# USB_TYPE_C.net
KiCad netlist of a schematic drawn in Altium Designer
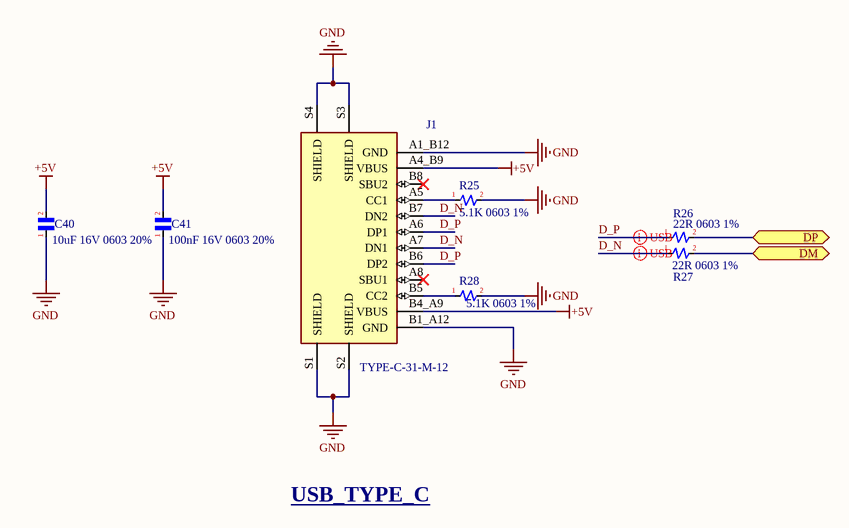
[diagram p0: USB_TYPE_C.SchDoc]

(export (version "E")
  (design (tool "Eeschema 10.0.6"))
  (components
    (comp (ref "C40")
      (value "10uF 16V 0603 20%")
      (footprint "C_0603")
      (description "CAP  0603 20%")
      (libsource (lib "Walton_EED") (part "Capacitor{gt}{gt} Non-Polar"))
    )
    (comp (ref "C41")
      (value "100nF 16V 0603 20%")
      (footprint "C_0603")
      (description "CAP  0603 20%")
      (libsource (lib "Walton_EED") (part "Capacitor{gt}{gt} Non-Polar"))
    )
    (comp (ref "J1")
      (value "TYPE-C-31-M-12")
      (footprint "HRO_TYPE-C-31-M-12")
      (description "USB Connectors 24 Receptacle 1 8.94*7.3mm RoHS")
      (fields (field (name "MF") "HRO Electronics Co., Ltd."))
      (libsource (lib "Walton_EED_13_05_2024") (part "TYPE-C-31-M-12"))
    )
    (comp (ref "R25")
      (value "5.1K 0603 1%")
      (footprint "R_0603")
      (description "RES 0603 20%")
      (libsource (lib "Walton_EED") (part "Resistor{gt}{gt} General Purpose"))
    )
    (comp (ref "R26")
      (value "22R 0603 1%")
      (footprint "R_0603")
      (description "RES 0603 20%")
      (libsource (lib "Walton_EED") (part "Resistor{gt}{gt} General Purpose"))
    )
    (comp (ref "R27")
      (value "22R 0603 1%")
      (footprint "R_0603")
      (description "RES 0603 20%")
      (libsource (lib "Walton_EED") (part "Resistor{gt}{gt} General Purpose"))
    )
    (comp (ref "R28")
      (value "5.1K 0603 1%")
      (footprint "R_0603")
      (description "RES 0603 20%")
      (libsource (lib "Walton_EED") (part "Resistor{gt}{gt} General Purpose"))
    )
  )
  (nets
    (net (code "1") (name "+5V") (class "Default")
      (node (ref "C40") (pin "2") (pinfunction "2_2") (pintype "passive"))
      (node (ref "C41") (pin "2") (pinfunction "2_2") (pintype "passive"))
      (node (ref "J1") (pin "A4_B9") (pinfunction "VBUS_A4_B9") (pintype "power_in"))
      (node (ref "J1") (pin "B4_A9") (pinfunction "VBUS_B4_A9") (pintype "power_in"))
    )
    (net (code "2") (name "/DM") (class "Default")
      (node (ref "R27") (pin "2") (pinfunction "2_2") (pintype "passive"))
    )
    (net (code "3") (name "/DP") (class "Default")
      (node (ref "R26") (pin "2") (pinfunction "2_2") (pintype "passive"))
    )
    (net (code "4") (name "/D_N") (class "Default")
      (node (ref "J1") (pin "A7") (pinfunction "DN1_A7") (pintype "bidirectional"))
      (node (ref "J1") (pin "B7") (pinfunction "DN2_B7") (pintype "bidirectional"))
      (node (ref "R27") (pin "1") (pinfunction "1_1") (pintype "passive"))
    )
    (net (code "5") (name "/D_P") (class "Default")
      (node (ref "J1") (pin "A6") (pinfunction "DP1_A6") (pintype "bidirectional"))
      (node (ref "J1") (pin "B6") (pinfunction "DP2_B6") (pintype "bidirectional"))
      (node (ref "R26") (pin "1") (pinfunction "1_1") (pintype "passive"))
    )
    (net (code "6") (name "GND") (class "Default")
      (node (ref "C40") (pin "1") (pinfunction "1_1") (pintype "passive"))
      (node (ref "C41") (pin "1") (pinfunction "1_1") (pintype "passive"))
      (node (ref "J1") (pin "A1_B12") (pinfunction "GND_A1_B12") (pintype "power_in"))
      (node (ref "J1") (pin "B1_A12") (pinfunction "GND_B1_A12") (pintype "power_in"))
      (node (ref "J1") (pin "S1") (pinfunction "SHIELD_S1") (pintype "passive"))
      (node (ref "J1") (pin "S2") (pinfunction "SHIELD_S2") (pintype "passive"))
      (node (ref "J1") (pin "S3") (pinfunction "SHIELD_S3") (pintype "passive"))
      (node (ref "J1") (pin "S4") (pinfunction "SHIELD_S4") (pintype "passive"))
      (node (ref "R25") (pin "2") (pinfunction "2_2") (pintype "passive"))
      (node (ref "R28") (pin "2") (pinfunction "2_2") (pintype "passive"))
    )
    (net (code "7") (name "Net-(J1-CC1)") (class "Default")
      (node (ref "J1") (pin "A5") (pinfunction "CC1_A5") (pintype "bidirectional"))
      (node (ref "R25") (pin "1") (pinfunction "1_1") (pintype "passive"))
    )
    (net (code "8") (name "Net-(J1-CC2)") (class "Default")
      (node (ref "J1") (pin "B5") (pinfunction "CC2_B5") (pintype "bidirectional"))
      (node (ref "R28") (pin "1") (pinfunction "1_1") (pintype "passive"))
    )
    (net (code "9") (name "unconnected-(J1-SBU1-PadA8)") (class "Default")
      (node (ref "J1") (pin "A8") (pinfunction "SBU1_A8") (pintype "bidirectional+no_connect"))
    )
    (net (code "10") (name "unconnected-(J1-SBU2-PadB8)") (class "Default")
      (node (ref "J1") (pin "B8") (pinfunction "SBU2_B8") (pintype "bidirectional+no_connect"))
    )
  )
)
